# pcb.net
KiCad netlist of a schematic drawn in EAGLE
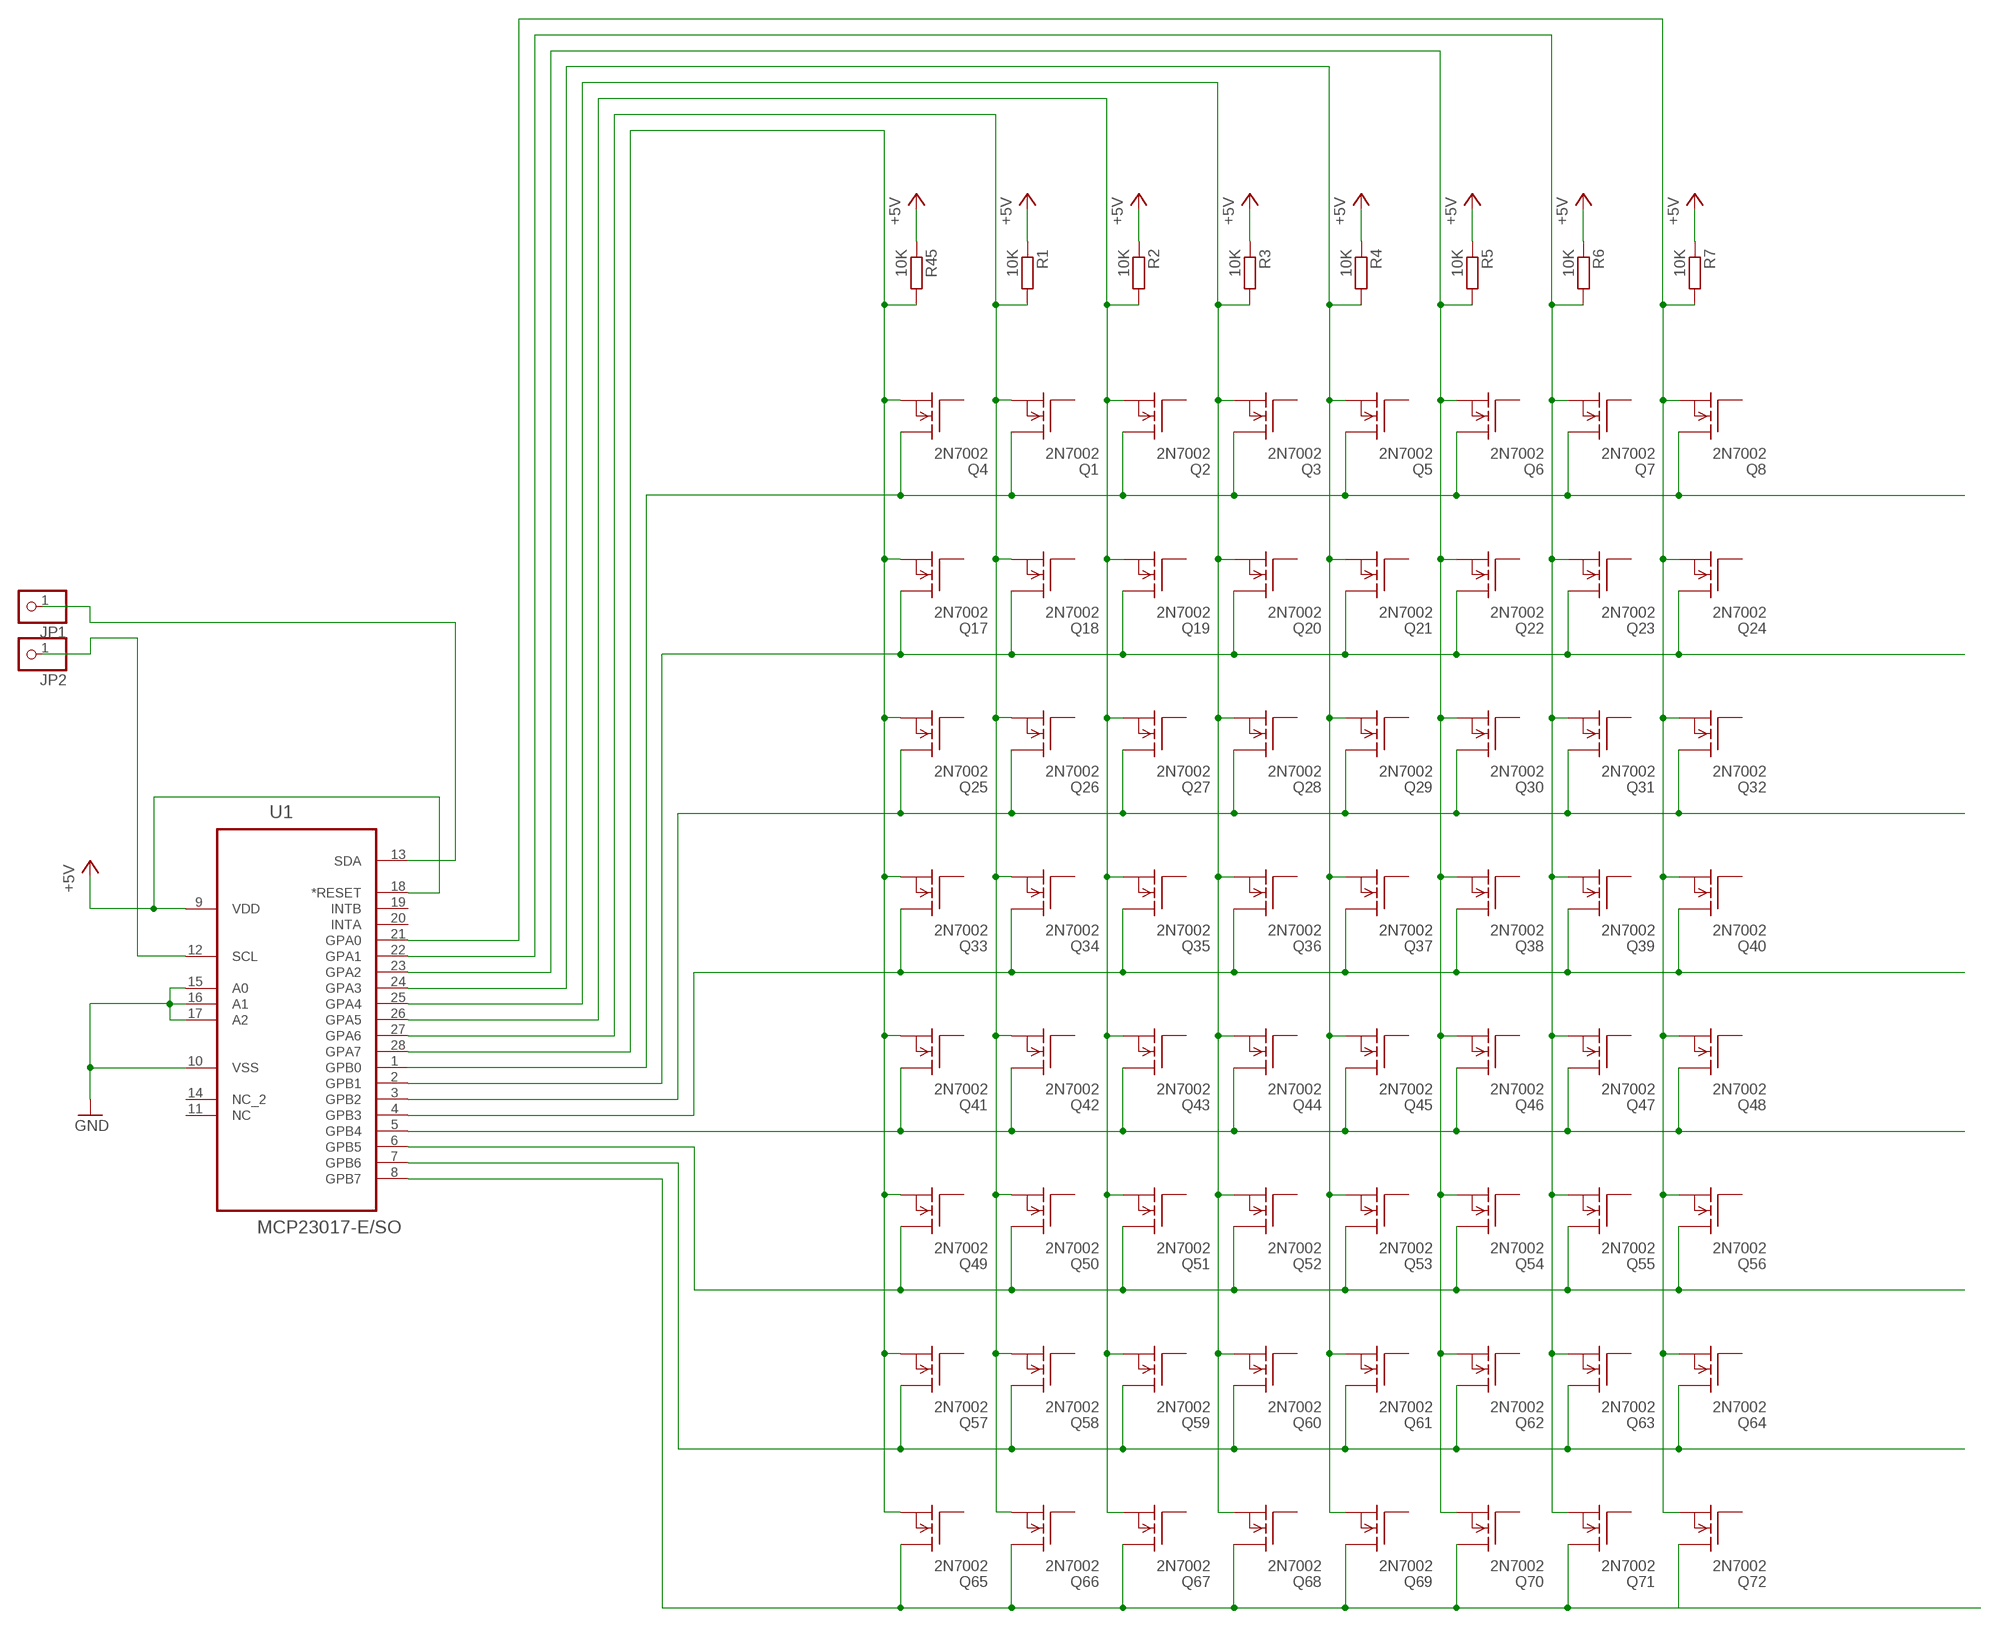
[diagram p0: schematic, sheet 1]

(export (version "E")
  (design (tool "Eeschema 10.0.6"))
  (components
    (comp (ref "JP1")
      (value "PINHD-1X1")
      (footprint "eagle-import:1X01")
      (libsource (lib "eagle-import") (part "PINHD-1X1"))
    )
    (comp (ref "JP2")
      (value "PINHD-1X1")
      (footprint "eagle-import:1X01")
      (libsource (lib "eagle-import") (part "PINHD-1X1"))
    )
    (comp (ref "Q1")
      (value "2N7002")
      (footprint "eagle-import:SOT23")
      (libsource (lib "eagle-import") (part "2N7002"))
    )
    (comp (ref "Q2")
      (value "2N7002")
      (footprint "eagle-import:SOT23")
      (libsource (lib "eagle-import") (part "2N7002"))
    )
    (comp (ref "Q3")
      (value "2N7002")
      (footprint "eagle-import:SOT23")
      (libsource (lib "eagle-import") (part "2N7002"))
    )
    (comp (ref "Q4")
      (value "2N7002")
      (footprint "eagle-import:SOT23")
      (libsource (lib "eagle-import") (part "2N7002"))
    )
    (comp (ref "Q5")
      (value "2N7002")
      (footprint "eagle-import:SOT23")
      (libsource (lib "eagle-import") (part "2N7002"))
    )
    (comp (ref "Q6")
      (value "2N7002")
      (footprint "eagle-import:SOT23")
      (libsource (lib "eagle-import") (part "2N7002"))
    )
    (comp (ref "Q7")
      (value "2N7002")
      (footprint "eagle-import:SOT23")
      (libsource (lib "eagle-import") (part "2N7002"))
    )
    (comp (ref "Q8")
      (value "2N7002")
      (footprint "eagle-import:SOT23")
      (libsource (lib "eagle-import") (part "2N7002"))
    )
    (comp (ref "Q17")
      (value "2N7002")
      (footprint "eagle-import:SOT23")
      (libsource (lib "eagle-import") (part "2N7002"))
    )
    (comp (ref "Q18")
      (value "2N7002")
      (footprint "eagle-import:SOT23")
      (libsource (lib "eagle-import") (part "2N7002"))
    )
    (comp (ref "Q19")
      (value "2N7002")
      (footprint "eagle-import:SOT23")
      (libsource (lib "eagle-import") (part "2N7002"))
    )
    (comp (ref "Q20")
      (value "2N7002")
      (footprint "eagle-import:SOT23")
      (libsource (lib "eagle-import") (part "2N7002"))
    )
    (comp (ref "Q21")
      (value "2N7002")
      (footprint "eagle-import:SOT23")
      (libsource (lib "eagle-import") (part "2N7002"))
    )
    (comp (ref "Q22")
      (value "2N7002")
      (footprint "eagle-import:SOT23")
      (libsource (lib "eagle-import") (part "2N7002"))
    )
    (comp (ref "Q23")
      (value "2N7002")
      (footprint "eagle-import:SOT23")
      (libsource (lib "eagle-import") (part "2N7002"))
    )
    (comp (ref "Q24")
      (value "2N7002")
      (footprint "eagle-import:SOT23")
      (libsource (lib "eagle-import") (part "2N7002"))
    )
    (comp (ref "Q25")
      (value "2N7002")
      (footprint "eagle-import:SOT23")
      (libsource (lib "eagle-import") (part "2N7002"))
    )
    (comp (ref "Q26")
      (value "2N7002")
      (footprint "eagle-import:SOT23")
      (libsource (lib "eagle-import") (part "2N7002"))
    )
    (comp (ref "Q27")
      (value "2N7002")
      (footprint "eagle-import:SOT23")
      (libsource (lib "eagle-import") (part "2N7002"))
    )
    (comp (ref "Q28")
      (value "2N7002")
      (footprint "eagle-import:SOT23")
      (libsource (lib "eagle-import") (part "2N7002"))
    )
    (comp (ref "Q29")
      (value "2N7002")
      (footprint "eagle-import:SOT23")
      (libsource (lib "eagle-import") (part "2N7002"))
    )
    (comp (ref "Q30")
      (value "2N7002")
      (footprint "eagle-import:SOT23")
      (libsource (lib "eagle-import") (part "2N7002"))
    )
    (comp (ref "Q31")
      (value "2N7002")
      (footprint "eagle-import:SOT23")
      (libsource (lib "eagle-import") (part "2N7002"))
    )
    (comp (ref "Q32")
      (value "2N7002")
      (footprint "eagle-import:SOT23")
      (libsource (lib "eagle-import") (part "2N7002"))
    )
    (comp (ref "Q33")
      (value "2N7002")
      (footprint "eagle-import:SOT23")
      (libsource (lib "eagle-import") (part "2N7002"))
    )
    (comp (ref "Q34")
      (value "2N7002")
      (footprint "eagle-import:SOT23")
      (libsource (lib "eagle-import") (part "2N7002"))
    )
    (comp (ref "Q35")
      (value "2N7002")
      (footprint "eagle-import:SOT23")
      (libsource (lib "eagle-import") (part "2N7002"))
    )
    (comp (ref "Q36")
      (value "2N7002")
      (footprint "eagle-import:SOT23")
      (libsource (lib "eagle-import") (part "2N7002"))
    )
    (comp (ref "Q37")
      (value "2N7002")
      (footprint "eagle-import:SOT23")
      (libsource (lib "eagle-import") (part "2N7002"))
    )
    (comp (ref "Q38")
      (value "2N7002")
      (footprint "eagle-import:SOT23")
      (libsource (lib "eagle-import") (part "2N7002"))
    )
    (comp (ref "Q39")
      (value "2N7002")
      (footprint "eagle-import:SOT23")
      (libsource (lib "eagle-import") (part "2N7002"))
    )
    (comp (ref "Q40")
      (value "2N7002")
      (footprint "eagle-import:SOT23")
      (libsource (lib "eagle-import") (part "2N7002"))
    )
    (comp (ref "Q41")
      (value "2N7002")
      (footprint "eagle-import:SOT23")
      (libsource (lib "eagle-import") (part "2N7002"))
    )
    (comp (ref "Q42")
      (value "2N7002")
      (footprint "eagle-import:SOT23")
      (libsource (lib "eagle-import") (part "2N7002"))
    )
    (comp (ref "Q43")
      (value "2N7002")
      (footprint "eagle-import:SOT23")
      (libsource (lib "eagle-import") (part "2N7002"))
    )
    (comp (ref "Q44")
      (value "2N7002")
      (footprint "eagle-import:SOT23")
      (libsource (lib "eagle-import") (part "2N7002"))
    )
    (comp (ref "Q45")
      (value "2N7002")
      (footprint "eagle-import:SOT23")
      (libsource (lib "eagle-import") (part "2N7002"))
    )
    (comp (ref "Q46")
      (value "2N7002")
      (footprint "eagle-import:SOT23")
      (libsource (lib "eagle-import") (part "2N7002"))
    )
    (comp (ref "Q47")
      (value "2N7002")
      (footprint "eagle-import:SOT23")
      (libsource (lib "eagle-import") (part "2N7002"))
    )
    (comp (ref "Q48")
      (value "2N7002")
      (footprint "eagle-import:SOT23")
      (libsource (lib "eagle-import") (part "2N7002"))
    )
    (comp (ref "Q49")
      (value "2N7002")
      (footprint "eagle-import:SOT23")
      (libsource (lib "eagle-import") (part "2N7002"))
    )
    (comp (ref "Q50")
      (value "2N7002")
      (footprint "eagle-import:SOT23")
      (libsource (lib "eagle-import") (part "2N7002"))
    )
    (comp (ref "Q51")
      (value "2N7002")
      (footprint "eagle-import:SOT23")
      (libsource (lib "eagle-import") (part "2N7002"))
    )
    (comp (ref "Q52")
      (value "2N7002")
      (footprint "eagle-import:SOT23")
      (libsource (lib "eagle-import") (part "2N7002"))
    )
    (comp (ref "Q53")
      (value "2N7002")
      (footprint "eagle-import:SOT23")
      (libsource (lib "eagle-import") (part "2N7002"))
    )
    (comp (ref "Q54")
      (value "2N7002")
      (footprint "eagle-import:SOT23")
      (libsource (lib "eagle-import") (part "2N7002"))
    )
    (comp (ref "Q55")
      (value "2N7002")
      (footprint "eagle-import:SOT23")
      (libsource (lib "eagle-import") (part "2N7002"))
    )
    (comp (ref "Q56")
      (value "2N7002")
      (footprint "eagle-import:SOT23")
      (libsource (lib "eagle-import") (part "2N7002"))
    )
    (comp (ref "Q57")
      (value "2N7002")
      (footprint "eagle-import:SOT23")
      (libsource (lib "eagle-import") (part "2N7002"))
    )
    (comp (ref "Q58")
      (value "2N7002")
      (footprint "eagle-import:SOT23")
      (libsource (lib "eagle-import") (part "2N7002"))
    )
    (comp (ref "Q59")
      (value "2N7002")
      (footprint "eagle-import:SOT23")
      (libsource (lib "eagle-import") (part "2N7002"))
    )
    (comp (ref "Q60")
      (value "2N7002")
      (footprint "eagle-import:SOT23")
      (libsource (lib "eagle-import") (part "2N7002"))
    )
    (comp (ref "Q61")
      (value "2N7002")
      (footprint "eagle-import:SOT23")
      (libsource (lib "eagle-import") (part "2N7002"))
    )
    (comp (ref "Q62")
      (value "2N7002")
      (footprint "eagle-import:SOT23")
      (libsource (lib "eagle-import") (part "2N7002"))
    )
    (comp (ref "Q63")
      (value "2N7002")
      (footprint "eagle-import:SOT23")
      (libsource (lib "eagle-import") (part "2N7002"))
    )
    (comp (ref "Q64")
      (value "2N7002")
      (footprint "eagle-import:SOT23")
      (libsource (lib "eagle-import") (part "2N7002"))
    )
    (comp (ref "Q65")
      (value "2N7002")
      (footprint "eagle-import:SOT23")
      (libsource (lib "eagle-import") (part "2N7002"))
    )
    (comp (ref "Q66")
      (value "2N7002")
      (footprint "eagle-import:SOT23")
      (libsource (lib "eagle-import") (part "2N7002"))
    )
    (comp (ref "Q67")
      (value "2N7002")
      (footprint "eagle-import:SOT23")
      (libsource (lib "eagle-import") (part "2N7002"))
    )
    (comp (ref "Q68")
      (value "2N7002")
      (footprint "eagle-import:SOT23")
      (libsource (lib "eagle-import") (part "2N7002"))
    )
    (comp (ref "Q69")
      (value "2N7002")
      (footprint "eagle-import:SOT23")
      (libsource (lib "eagle-import") (part "2N7002"))
    )
    (comp (ref "Q70")
      (value "2N7002")
      (footprint "eagle-import:SOT23")
      (libsource (lib "eagle-import") (part "2N7002"))
    )
    (comp (ref "Q71")
      (value "2N7002")
      (footprint "eagle-import:SOT23")
      (libsource (lib "eagle-import") (part "2N7002"))
    )
    (comp (ref "Q72")
      (value "2N7002")
      (footprint "eagle-import:SOT23")
      (libsource (lib "eagle-import") (part "2N7002"))
    )
    (comp (ref "R1")
      (value "10K")
      (footprint "eagle-import:R0805")
      (libsource (lib "eagle-import") (part "R-EU_R0805"))
    )
    (comp (ref "R2")
      (value "10K")
      (footprint "eagle-import:R0805")
      (libsource (lib "eagle-import") (part "R-EU_R0805"))
    )
    (comp (ref "R3")
      (value "10K")
      (footprint "eagle-import:R0805")
      (libsource (lib "eagle-import") (part "R-EU_R0805"))
    )
    (comp (ref "R4")
      (value "10K")
      (footprint "eagle-import:R0805")
      (libsource (lib "eagle-import") (part "R-EU_R0805"))
    )
    (comp (ref "R5")
      (value "10K")
      (footprint "eagle-import:R0805")
      (libsource (lib "eagle-import") (part "R-EU_R0805"))
    )
    (comp (ref "R6")
      (value "10K")
      (footprint "eagle-import:R0805")
      (libsource (lib "eagle-import") (part "R-EU_R0805"))
    )
    (comp (ref "R7")
      (value "10K")
      (footprint "eagle-import:R0805")
      (libsource (lib "eagle-import") (part "R-EU_R0805"))
    )
    (comp (ref "R45")
      (value "10K")
      (footprint "eagle-import:R0805")
      (libsource (lib "eagle-import") (part "R-EU_R0805"))
    )
    (comp (ref "U1")
      (value "MCP23017-E/SO")
      (footprint "eagle-import:SOIC127P1032X265-28N")
      (libsource (lib "eagle-import") (part "MCP23017-E/SO"))
    )
  )
  (nets
    (net (code "1") (name "+5V") (class "Default")
      (node (ref "R1") (pin "1") (pinfunction "1_1") (pintype "passive"))
      (node (ref "R2") (pin "1") (pinfunction "1_1") (pintype "passive"))
      (node (ref "R3") (pin "1") (pinfunction "1_1") (pintype "passive"))
      (node (ref "R4") (pin "1") (pinfunction "1_1") (pintype "passive"))
      (node (ref "R45") (pin "1") (pinfunction "1_1") (pintype "passive"))
      (node (ref "R5") (pin "1") (pinfunction "1_1") (pintype "passive"))
      (node (ref "R6") (pin "1") (pinfunction "1_1") (pintype "passive"))
      (node (ref "R7") (pin "1") (pinfunction "1_1") (pintype "passive"))
      (node (ref "U1") (pin "18") (pinfunction "*RESET_18") (pintype "output"))
      (node (ref "U1") (pin "9") (pinfunction "VDD_9") (pintype "power_in"))
    )
    (net (code "2") (name "GND") (class "Default")
      (node (ref "U1") (pin "10") (pinfunction "VSS_10") (pintype "power_in"))
      (node (ref "U1") (pin "15") (pinfunction "A0_15") (pintype "input"))
      (node (ref "U1") (pin "16") (pinfunction "A1_16") (pintype "input"))
      (node (ref "U1") (pin "17") (pinfunction "A2_17") (pintype "input"))
    )
    (net (code "3") (name "Net-(Q1-D)") (class "Default")
      (node (ref "Q1") (pin "3") (pinfunction "D_3") (pintype "passive"))
      (node (ref "Q2") (pin "3") (pinfunction "D_3") (pintype "passive"))
      (node (ref "Q3") (pin "3") (pinfunction "D_3") (pintype "passive"))
      (node (ref "Q4") (pin "3") (pinfunction "D_3") (pintype "passive"))
      (node (ref "Q5") (pin "3") (pinfunction "D_3") (pintype "passive"))
      (node (ref "Q6") (pin "3") (pinfunction "D_3") (pintype "passive"))
      (node (ref "Q7") (pin "3") (pinfunction "D_3") (pintype "passive"))
      (node (ref "Q8") (pin "3") (pinfunction "D_3") (pintype "passive"))
      (node (ref "U1") (pin "1") (pinfunction "GPB0_1") (pintype "bidirectional"))
    )
    (net (code "4") (name "Net-(Q1-S)") (class "Default")
      (node (ref "Q1") (pin "2") (pinfunction "S_2") (pintype "passive"))
      (node (ref "Q18") (pin "2") (pinfunction "S_2") (pintype "passive"))
      (node (ref "Q26") (pin "2") (pinfunction "S_2") (pintype "passive"))
      (node (ref "Q34") (pin "2") (pinfunction "S_2") (pintype "passive"))
      (node (ref "Q42") (pin "2") (pinfunction "S_2") (pintype "passive"))
      (node (ref "Q50") (pin "2") (pinfunction "S_2") (pintype "passive"))
      (node (ref "Q58") (pin "2") (pinfunction "S_2") (pintype "passive"))
      (node (ref "Q66") (pin "2") (pinfunction "S_2") (pintype "passive"))
      (node (ref "R1") (pin "2") (pinfunction "2_2") (pintype "passive"))
      (node (ref "U1") (pin "27") (pinfunction "GPA6_27") (pintype "bidirectional"))
    )
    (net (code "5") (name "Net-(Q17-D)") (class "Default")
      (node (ref "Q17") (pin "3") (pinfunction "D_3") (pintype "passive"))
      (node (ref "Q18") (pin "3") (pinfunction "D_3") (pintype "passive"))
      (node (ref "Q19") (pin "3") (pinfunction "D_3") (pintype "passive"))
      (node (ref "Q20") (pin "3") (pinfunction "D_3") (pintype "passive"))
      (node (ref "Q21") (pin "3") (pinfunction "D_3") (pintype "passive"))
      (node (ref "Q22") (pin "3") (pinfunction "D_3") (pintype "passive"))
      (node (ref "Q23") (pin "3") (pinfunction "D_3") (pintype "passive"))
      (node (ref "Q24") (pin "3") (pinfunction "D_3") (pintype "passive"))
      (node (ref "U1") (pin "2") (pinfunction "GPB1_2") (pintype "bidirectional"))
    )
    (net (code "6") (name "Net-(Q17-S)") (class "Default")
      (node (ref "Q17") (pin "2") (pinfunction "S_2") (pintype "passive"))
      (node (ref "Q25") (pin "2") (pinfunction "S_2") (pintype "passive"))
      (node (ref "Q33") (pin "2") (pinfunction "S_2") (pintype "passive"))
      (node (ref "Q4") (pin "2") (pinfunction "S_2") (pintype "passive"))
      (node (ref "Q41") (pin "2") (pinfunction "S_2") (pintype "passive"))
      (node (ref "Q49") (pin "2") (pinfunction "S_2") (pintype "passive"))
      (node (ref "Q57") (pin "2") (pinfunction "S_2") (pintype "passive"))
      (node (ref "Q65") (pin "2") (pinfunction "S_2") (pintype "passive"))
      (node (ref "R45") (pin "2") (pinfunction "2_2") (pintype "passive"))
      (node (ref "U1") (pin "28") (pinfunction "GPA7_28") (pintype "bidirectional"))
    )
    (net (code "7") (name "Net-(Q19-S)") (class "Default")
      (node (ref "Q19") (pin "2") (pinfunction "S_2") (pintype "passive"))
      (node (ref "Q2") (pin "2") (pinfunction "S_2") (pintype "passive"))
      (node (ref "Q27") (pin "2") (pinfunction "S_2") (pintype "passive"))
      (node (ref "Q35") (pin "2") (pinfunction "S_2") (pintype "passive"))
      (node (ref "Q43") (pin "2") (pinfunction "S_2") (pintype "passive"))
      (node (ref "Q51") (pin "2") (pinfunction "S_2") (pintype "passive"))
      (node (ref "Q59") (pin "2") (pinfunction "S_2") (pintype "passive"))
      (node (ref "Q67") (pin "2") (pinfunction "S_2") (pintype "passive"))
      (node (ref "R2") (pin "2") (pinfunction "2_2") (pintype "passive"))
      (node (ref "U1") (pin "26") (pinfunction "GPA5_26") (pintype "bidirectional"))
    )
    (net (code "8") (name "Net-(Q20-S)") (class "Default")
      (node (ref "Q20") (pin "2") (pinfunction "S_2") (pintype "passive"))
      (node (ref "Q28") (pin "2") (pinfunction "S_2") (pintype "passive"))
      (node (ref "Q3") (pin "2") (pinfunction "S_2") (pintype "passive"))
      (node (ref "Q36") (pin "2") (pinfunction "S_2") (pintype "passive"))
      (node (ref "Q44") (pin "2") (pinfunction "S_2") (pintype "passive"))
      (node (ref "Q52") (pin "2") (pinfunction "S_2") (pintype "passive"))
      (node (ref "Q60") (pin "2") (pinfunction "S_2") (pintype "passive"))
      (node (ref "Q68") (pin "2") (pinfunction "S_2") (pintype "passive"))
      (node (ref "R3") (pin "2") (pinfunction "2_2") (pintype "passive"))
      (node (ref "U1") (pin "25") (pinfunction "GPA4_25") (pintype "bidirectional"))
    )
    (net (code "9") (name "Net-(Q21-S)") (class "Default")
      (node (ref "Q21") (pin "2") (pinfunction "S_2") (pintype "passive"))
      (node (ref "Q29") (pin "2") (pinfunction "S_2") (pintype "passive"))
      (node (ref "Q37") (pin "2") (pinfunction "S_2") (pintype "passive"))
      (node (ref "Q45") (pin "2") (pinfunction "S_2") (pintype "passive"))
      (node (ref "Q5") (pin "2") (pinfunction "S_2") (pintype "passive"))
      (node (ref "Q53") (pin "2") (pinfunction "S_2") (pintype "passive"))
      (node (ref "Q61") (pin "2") (pinfunction "S_2") (pintype "passive"))
      (node (ref "Q69") (pin "2") (pinfunction "S_2") (pintype "passive"))
      (node (ref "R4") (pin "2") (pinfunction "2_2") (pintype "passive"))
      (node (ref "U1") (pin "24") (pinfunction "GPA3_24") (pintype "bidirectional"))
    )
    (net (code "10") (name "Net-(Q22-S)") (class "Default")
      (node (ref "Q22") (pin "2") (pinfunction "S_2") (pintype "passive"))
      (node (ref "Q30") (pin "2") (pinfunction "S_2") (pintype "passive"))
      (node (ref "Q38") (pin "2") (pinfunction "S_2") (pintype "passive"))
      (node (ref "Q46") (pin "2") (pinfunction "S_2") (pintype "passive"))
      (node (ref "Q54") (pin "2") (pinfunction "S_2") (pintype "passive"))
      (node (ref "Q6") (pin "2") (pinfunction "S_2") (pintype "passive"))
      (node (ref "Q62") (pin "2") (pinfunction "S_2") (pintype "passive"))
      (node (ref "Q70") (pin "2") (pinfunction "S_2") (pintype "passive"))
      (node (ref "R5") (pin "2") (pinfunction "2_2") (pintype "passive"))
      (node (ref "U1") (pin "23") (pinfunction "GPA2_23") (pintype "bidirectional"))
    )
    (net (code "11") (name "Net-(Q23-S)") (class "Default")
      (node (ref "Q23") (pin "2") (pinfunction "S_2") (pintype "passive"))
      (node (ref "Q31") (pin "2") (pinfunction "S_2") (pintype "passive"))
      (node (ref "Q39") (pin "2") (pinfunction "S_2") (pintype "passive"))
      (node (ref "Q47") (pin "2") (pinfunction "S_2") (pintype "passive"))
      (node (ref "Q55") (pin "2") (pinfunction "S_2") (pintype "passive"))
      (node (ref "Q63") (pin "2") (pinfunction "S_2") (pintype "passive"))
      (node (ref "Q7") (pin "2") (pinfunction "S_2") (pintype "passive"))
      (node (ref "Q71") (pin "2") (pinfunction "S_2") (pintype "passive"))
      (node (ref "R6") (pin "2") (pinfunction "2_2") (pintype "passive"))
      (node (ref "U1") (pin "22") (pinfunction "GPA1_22") (pintype "bidirectional"))
    )
    (net (code "12") (name "Net-(Q24-S)") (class "Default")
      (node (ref "Q24") (pin "2") (pinfunction "S_2") (pintype "passive"))
      (node (ref "Q32") (pin "2") (pinfunction "S_2") (pintype "passive"))
      (node (ref "Q40") (pin "2") (pinfunction "S_2") (pintype "passive"))
      (node (ref "Q48") (pin "2") (pinfunction "S_2") (pintype "passive"))
      (node (ref "Q56") (pin "2") (pinfunction "S_2") (pintype "passive"))
      (node (ref "Q64") (pin "2") (pinfunction "S_2") (pintype "passive"))
      (node (ref "Q72") (pin "2") (pinfunction "S_2") (pintype "passive"))
      (node (ref "Q8") (pin "2") (pinfunction "S_2") (pintype "passive"))
      (node (ref "R7") (pin "2") (pinfunction "2_2") (pintype "passive"))
      (node (ref "U1") (pin "21") (pinfunction "GPA0_21") (pintype "bidirectional"))
    )
    (net (code "13") (name "Net-(Q25-D)") (class "Default")
      (node (ref "Q25") (pin "3") (pinfunction "D_3") (pintype "passive"))
      (node (ref "Q26") (pin "3") (pinfunction "D_3") (pintype "passive"))
      (node (ref "Q27") (pin "3") (pinfunction "D_3") (pintype "passive"))
      (node (ref "Q28") (pin "3") (pinfunction "D_3") (pintype "passive"))
      (node (ref "Q29") (pin "3") (pinfunction "D_3") (pintype "passive"))
      (node (ref "Q30") (pin "3") (pinfunction "D_3") (pintype "passive"))
      (node (ref "Q31") (pin "3") (pinfunction "D_3") (pintype "passive"))
      (node (ref "Q32") (pin "3") (pinfunction "D_3") (pintype "passive"))
      (node (ref "U1") (pin "3") (pinfunction "GPB2_3") (pintype "bidirectional"))
    )
    (net (code "14") (name "Net-(Q33-D)") (class "Default")
      (node (ref "Q33") (pin "3") (pinfunction "D_3") (pintype "passive"))
      (node (ref "Q34") (pin "3") (pinfunction "D_3") (pintype "passive"))
      (node (ref "Q35") (pin "3") (pinfunction "D_3") (pintype "passive"))
      (node (ref "Q36") (pin "3") (pinfunction "D_3") (pintype "passive"))
      (node (ref "Q37") (pin "3") (pinfunction "D_3") (pintype "passive"))
      (node (ref "Q38") (pin "3") (pinfunction "D_3") (pintype "passive"))
      (node (ref "Q39") (pin "3") (pinfunction "D_3") (pintype "passive"))
      (node (ref "Q40") (pin "3") (pinfunction "D_3") (pintype "passive"))
      (node (ref "U1") (pin "4") (pinfunction "GPB3_4") (pintype "bidirectional"))
    )
    (net (code "15") (name "Net-(Q41-D)") (class "Default")
      (node (ref "Q41") (pin "3") (pinfunction "D_3") (pintype "passive"))
      (node (ref "Q42") (pin "3") (pinfunction "D_3") (pintype "passive"))
      (node (ref "Q43") (pin "3") (pinfunction "D_3") (pintype "passive"))
      (node (ref "Q44") (pin "3") (pinfunction "D_3") (pintype "passive"))
      (node (ref "Q45") (pin "3") (pinfunction "D_3") (pintype "passive"))
      (node (ref "Q46") (pin "3") (pinfunction "D_3") (pintype "passive"))
      (node (ref "Q47") (pin "3") (pinfunction "D_3") (pintype "passive"))
      (node (ref "Q48") (pin "3") (pinfunction "D_3") (pintype "passive"))
      (node (ref "U1") (pin "5") (pinfunction "GPB4_5") (pintype "bidirectional"))
    )
    (net (code "16") (name "Net-(Q49-D)") (class "Default")
      (node (ref "Q49") (pin "3") (pinfunction "D_3") (pintype "passive"))
      (node (ref "Q50") (pin "3") (pinfunction "D_3") (pintype "passive"))
      (node (ref "Q51") (pin "3") (pinfunction "D_3") (pintype "passive"))
      (node (ref "Q52") (pin "3") (pinfunction "D_3") (pintype "passive"))
      (node (ref "Q53") (pin "3") (pinfunction "D_3") (pintype "passive"))
      (node (ref "Q54") (pin "3") (pinfunction "D_3") (pintype "passive"))
      (node (ref "Q55") (pin "3") (pinfunction "D_3") (pintype "passive"))
      (node (ref "Q56") (pin "3") (pinfunction "D_3") (pintype "passive"))
      (node (ref "U1") (pin "6") (pinfunction "GPB5_6") (pintype "bidirectional"))
    )
    (net (code "17") (name "Net-(Q57-D)") (class "Default")
      (node (ref "Q57") (pin "3") (pinfunction "D_3") (pintype "passive"))
      (node (ref "Q58") (pin "3") (pinfunction "D_3") (pintype "passive"))
      (node (ref "Q59") (pin "3") (pinfunction "D_3") (pintype "passive"))
      (node (ref "Q60") (pin "3") (pinfunction "D_3") (pintype "passive"))
      (node (ref "Q61") (pin "3") (pinfunction "D_3") (pintype "passive"))
      (node (ref "Q62") (pin "3") (pinfunction "D_3") (pintype "passive"))
      (node (ref "Q63") (pin "3") (pinfunction "D_3") (pintype "passive"))
      (node (ref "Q64") (pin "3") (pinfunction "D_3") (pintype "passive"))
      (node (ref "U1") (pin "7") (pinfunction "GPB6_7") (pintype "bidirectional"))
    )
    (net (code "18") (name "Net-(Q65-D)") (class "Default")
      (node (ref "Q65") (pin "3") (pinfunction "D_3") (pintype "passive"))
      (node (ref "Q66") (pin "3") (pinfunction "D_3") (pintype "passive"))
      (node (ref "Q67") (pin "3") (pinfunction "D_3") (pintype "passive"))
      (node (ref "Q68") (pin "3") (pinfunction "D_3") (pintype "passive"))
      (node (ref "Q69") (pin "3") (pinfunction "D_3") (pintype "passive"))
      (node (ref "Q70") (pin "3") (pinfunction "D_3") (pintype "passive"))
      (node (ref "Q71") (pin "3") (pinfunction "D_3") (pintype "passive"))
      (node (ref "Q72") (pin "3") (pinfunction "D_3") (pintype "passive"))
      (node (ref "U1") (pin "8") (pinfunction "GPB7_8") (pintype "bidirectional"))
    )
    (net (code "19") (name "Net-(U1-SCL)") (class "Default")
      (node (ref "JP2") (pin "1") (pinfunction "1_1") (pintype "passive"))
      (node (ref "U1") (pin "12") (pinfunction "SCL_12") (pintype "input"))
    )
    (net (code "20") (name "Net-(U1-SDA)") (class "Default")
      (node (ref "JP1") (pin "1") (pinfunction "1_1") (pintype "passive"))
      (node (ref "U1") (pin "13") (pinfunction "SDA_13") (pintype "bidirectional"))
    )
    (net (code "21") (name "unconnected-(Q1-G-Pad1)") (class "Default")
      (node (ref "Q1") (pin "1") (pinfunction "G_1") (pintype "passive"))
    )
    (net (code "22") (name "unconnected-(Q2-G-Pad1)") (class "Default")
      (node (ref "Q2") (pin "1") (pinfunction "G_1") (pintype "passive"))
    )
    (net (code "23") (name "unconnected-(Q3-G-Pad1)") (class "Default")
      (node (ref "Q3") (pin "1") (pinfunction "G_1") (pintype "passive"))
    )
    (net (code "24") (name "unconnected-(Q4-G-Pad1)") (class "Default")
      (node (ref "Q4") (pin "1") (pinfunction "G_1") (pintype "passive"))
    )
    (net (code "25") (name "unconnected-(Q5-G-Pad1)") (class "Default")
      (node (ref "Q5") (pin "1") (pinfunction "G_1") (pintype "passive"))
    )
    (net (code "26") (name "unconnected-(Q6-G-Pad1)") (class "Default")
      (node (ref "Q6") (pin "1") (pinfunction "G_1") (pintype "passive"))
    )
    (net (code "27") (name "unconnected-(Q7-G-Pad1)") (class "Default")
      (node (ref "Q7") (pin "1") (pinfunction "G_1") (pintype "passive"))
    )
    (net (code "28") (name "unconnected-(Q8-G-Pad1)") (class "Default")
      (node (ref "Q8") (pin "1") (pinfunction "G_1") (pintype "passive"))
    )
    (net (code "29") (name "unconnected-(Q17-G-Pad1)") (class "Default")
      (node (ref "Q17") (pin "1") (pinfunction "G_1") (pintype "passive"))
    )
    (net (code "30") (name "unconnected-(Q18-G-Pad1)") (class "Default")
      (node (ref "Q18") (pin "1") (pinfunction "G_1") (pintype "passive"))
    )
    (net (code "31") (name "unconnected-(Q19-G-Pad1)") (class "Default")
      (node (ref "Q19") (pin "1") (pinfunction "G_1") (pintype "passive"))
    )
    (net (code "32") (name "unconnected-(Q20-G-Pad1)") (class "Default")
      (node (ref "Q20") (pin "1") (pinfunction "G_1") (pintype "passive"))
    )
    (net (code "33") (name "unconnected-(Q21-G-Pad1)") (class "Default")
      (node (ref "Q21") (pin "1") (pinfunction "G_1") (pintype "passive"))
    )
    (net (code "34") (name "unconnected-(Q22-G-Pad1)") (class "Default")
      (node (ref "Q22") (pin "1") (pinfunction "G_1") (pintype "passive"))
    )
    (net (code "35") (name "unconnected-(Q23-G-Pad1)") (class "Default")
      (node (ref "Q23") (pin "1") (pinfunction "G_1") (pintype "passive"))
    )
    (net (code "36") (name "unconnected-(Q24-G-Pad1)") (class "Default")
      (node (ref "Q24") (pin "1") (pinfunction "G_1") (pintype "passive"))
    )
    (net (code "37") (name "unconnected-(Q25-G-Pad1)") (class "Default")
      (node (ref "Q25") (pin "1") (pinfunction "G_1") (pintype "passive"))
    )
    (net (code "38") (name "unconnected-(Q26-G-Pad1)") (class "Default")
      (node (ref "Q26") (pin "1") (pinfunction "G_1") (pintype "passive"))
    )
    (net (code "39") (name "unconnected-(Q27-G-Pad1)") (class "Default")
      (node (ref "Q27") (pin "1") (pinfunction "G_1") (pintype "passive"))
    )
    (net (code "40") (name "unconnected-(Q28-G-Pad1)") (class "Default")
      (node (ref "Q28") (pin "1") (pinfunction "G_1") (pintype "passive"))
    )
    (net (code "41") (name "unconnected-(Q29-G-Pad1)") (class "Default")
      (node (ref "Q29") (pin "1") (pinfunction "G_1") (pintype "passive"))
    )
    (net (code "42") (name "unconnected-(Q30-G-Pad1)") (class "Default")
      (node (ref "Q30") (pin "1") (pinfunction "G_1") (pintype "passive"))
    )
    (net (code "43") (name "unconnected-(Q31-G-Pad1)") (class "Default")
      (node (ref "Q31") (pin "1") (pinfunction "G_1") (pintype "passive"))
    )
    (net (code "44") (name "unconnected-(Q32-G-Pad1)") (class "Default")
      (node (ref "Q32") (pin "1") (pinfunction "G_1") (pintype "passive"))
    )
    (net (code "45") (name "unconnected-(Q33-G-Pad1)") (class "Default")
      (node (ref "Q33") (pin "1") (pinfunction "G_1") (pintype "passive"))
    )
    (net (code "46") (name "unconnected-(Q34-G-Pad1)") (class "Default")
      (node (ref "Q34") (pin "1") (pinfunction "G_1") (pintype "passive"))
    )
    (net (code "47") (name "unconnected-(Q35-G-Pad1)") (class "Default")
      (node (ref "Q35") (pin "1") (pinfunction "G_1") (pintype "passive"))
    )
    (net (code "48") (name "unconnected-(Q36-G-Pad1)") (class "Default")
      (node (ref "Q36") (pin "1") (pinfunction "G_1") (pintype "passive"))
    )
    (net (code "49") (name "unconnected-(Q37-G-Pad1)") (class "Default")
      (node (ref "Q37") (pin "1") (pinfunction "G_1") (pintype "passive"))
    )
    (net (code "50") (name "unconnected-(Q38-G-Pad1)") (class "Default")
      (node (ref "Q38") (pin "1") (pinfunction "G_1") (pintype "passive"))
    )
    (net (code "51") (name "unconnected-(Q39-G-Pad1)") (class "Default")
      (node (ref "Q39") (pin "1") (pinfunction "G_1") (pintype "passive"))
    )
    (net (code "52") (name "unconnected-(Q40-G-Pad1)") (class "Default")
      (node (ref "Q40") (pin "1") (pinfunction "G_1") (pintype "passive"))
    )
    (net (code "53") (name "unconnected-(Q41-G-Pad1)") (class "Default")
      (node (ref "Q41") (pin "1") (pinfunction "G_1") (pintype "passive"))
    )
    (net (code "54") (name "unconnected-(Q42-G-Pad1)") (class "Default")
      (node (ref "Q42") (pin "1") (pinfunction "G_1") (pintype "passive"))
    )
    (net (code "55") (name "unconnected-(Q43-G-Pad1)") (class "Default")
      (node (ref "Q43") (pin "1") (pinfunction "G_1") (pintype "passive"))
    )
    (net (code "56") (name "unconnected-(Q44-G-Pad1)") (class "Default")
      (node (ref "Q44") (pin "1") (pinfunction "G_1") (pintype "passive"))
    )
    (net (code "57") (name "unconnected-(Q45-G-Pad1)") (class "Default")
      (node (ref "Q45") (pin "1") (pinfunction "G_1") (pintype "passive"))
    )
    (net (code "58") (name "unconnected-(Q46-G-Pad1)") (class "Default")
      (node (ref "Q46") (pin "1") (pinfunction "G_1") (pintype "passive"))
    )
    (net (code "59") (name "unconnected-(Q47-G-Pad1)") (class "Default")
      (node (ref "Q47") (pin "1") (pinfunction "G_1") (pintype "passive"))
    )
    (net (code "60") (name "unconnected-(Q48-G-Pad1)") (class "Default")
      (node (ref "Q48") (pin "1") (pinfunction "G_1") (pintype "passive"))
    )
    (net (code "61") (name "unconnected-(Q49-G-Pad1)") (class "Default")
      (node (ref "Q49") (pin "1") (pinfunction "G_1") (pintype "passive"))
    )
    (net (code "62") (name "unconnected-(Q50-G-Pad1)") (class "Default")
      (node (ref "Q50") (pin "1") (pinfunction "G_1") (pintype "passive"))
    )
    (net (code "63") (name "unconnected-(Q51-G-Pad1)") (class "Default")
      (node (ref "Q51") (pin "1") (pinfunction "G_1") (pintype "passive"))
    )
    (net (code "64") (name "unconnected-(Q52-G-Pad1)") (class "Default")
      (node (ref "Q52") (pin "1") (pinfunction "G_1") (pintype "passive"))
    )
    (net (code "65") (name "unconnected-(Q53-G-Pad1)") (class "Default")
      (node (ref "Q53") (pin "1") (pinfunction "G_1") (pintype "passive"))
    )
    (net (code "66") (name "unconnected-(Q54-G-Pad1)") (class "Default")
      (node (ref "Q54") (pin "1") (pinfunction "G_1") (pintype "passive"))
    )
    (net (code "67") (name "unconnected-(Q55-G-Pad1)") (class "Default")
      (node (ref "Q55") (pin "1") (pinfunction "G_1") (pintype "passive"))
    )
    (net (code "68") (name "unconnected-(Q56-G-Pad1)") (class "Default")
      (node (ref "Q56") (pin "1") (pinfunction "G_1") (pintype "passive"))
    )
    (net (code "69") (name "unconnected-(Q57-G-Pad1)") (class "Default")
      (node (ref "Q57") (pin "1") (pinfunction "G_1") (pintype "passive"))
    )
    (net (code "70") (name "unconnected-(Q58-G-Pad1)") (class "Default")
      (node (ref "Q58") (pin "1") (pinfunction "G_1") (pintype "passive"))
    )
    (net (code "71") (name "unconnected-(Q59-G-Pad1)") (class "Default")
      (node (ref "Q59") (pin "1") (pinfunction "G_1") (pintype "passive"))
    )
    (net (code "72") (name "unconnected-(Q60-G-Pad1)") (class "Default")
      (node (ref "Q60") (pin "1") (pinfunction "G_1") (pintype "passive"))
    )
    (net (code "73") (name "unconnected-(Q61-G-Pad1)") (class "Default")
      (node (ref "Q61") (pin "1") (pinfunction "G_1") (pintype "passive"))
    )
    (net (code "74") (name "unconnected-(Q62-G-Pad1)") (class "Default")
      (node (ref "Q62") (pin "1") (pinfunction "G_1") (pintype "passive"))
    )
    (net (code "75") (name "unconnected-(Q63-G-Pad1)") (class "Default")
      (node (ref "Q63") (pin "1") (pinfunction "G_1") (pintype "passive"))
    )
    (net (code "76") (name "unconnected-(Q64-G-Pad1)") (class "Default")
      (node (ref "Q64") (pin "1") (pinfunction "G_1") (pintype "passive"))
    )
    (net (code "77") (name "unconnected-(Q65-G-Pad1)") (class "Default")
      (node (ref "Q65") (pin "1") (pinfunction "G_1") (pintype "passive"))
    )
    (net (code "78") (name "unconnected-(Q66-G-Pad1)") (class "Default")
      (node (ref "Q66") (pin "1") (pinfunction "G_1") (pintype "passive"))
    )
    (net (code "79") (name "unconnected-(Q67-G-Pad1)") (class "Default")
      (node (ref "Q67") (pin "1") (pinfunction "G_1") (pintype "passive"))
    )
    (net (code "80") (name "unconnected-(Q68-G-Pad1)") (class "Default")
      (node (ref "Q68") (pin "1") (pinfunction "G_1") (pintype "passive"))
    )
    (net (code "81") (name "unconnected-(Q69-G-Pad1)") (class "Default")
      (node (ref "Q69") (pin "1") (pinfunction "G_1") (pintype "passive"))
    )
    (net (code "82") (name "unconnected-(Q70-G-Pad1)") (class "Default")
      (node (ref "Q70") (pin "1") (pinfunction "G_1") (pintype "passive"))
    )
    (net (code "83") (name "unconnected-(Q71-G-Pad1)") (class "Default")
      (node (ref "Q71") (pin "1") (pinfunction "G_1") (pintype "passive"))
    )
    (net (code "84") (name "unconnected-(Q72-G-Pad1)") (class "Default")
      (node (ref "Q72") (pin "1") (pinfunction "G_1") (pintype "passive"))
    )
    (net (code "85") (name "unconnected-(U1-INTA-Pad20)") (class "Default")
      (node (ref "U1") (pin "20") (pinfunction "INTA_20") (pintype "output"))
    )
    (net (code "86") (name "unconnected-(U1-INTB-Pad19)") (class "Default")
      (node (ref "U1") (pin "19") (pinfunction "INTB_19") (pintype "output"))
    )
    (net (code "87") (name "unconnected-(U1-NC-Pad11)") (class "Default")
      (node (ref "U1") (pin "11") (pinfunction "NC_11") (pintype "no_connect"))
    )
    (net (code "88") (name "unconnected-(U1-NC_2-Pad14)") (class "Default")
      (node (ref "U1") (pin "14") (pinfunction "NC_2_14") (pintype "no_connect"))
    )
  )
)
